# CAN_5V.net
KiCad netlist of a schematic drawn in Altium Designer
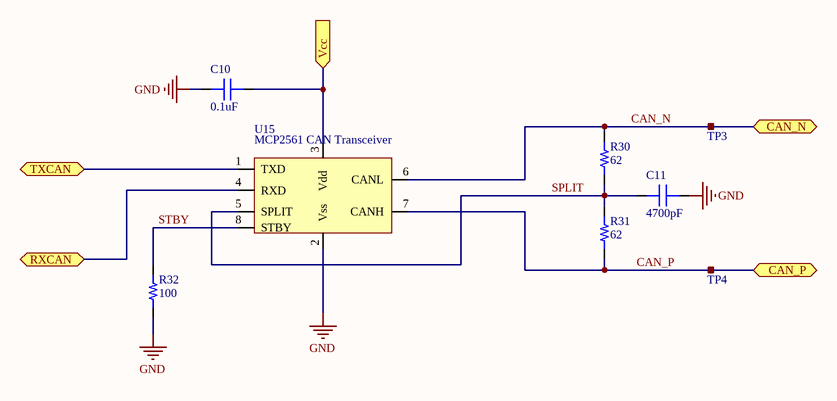
[diagram p0: CAN_5V.SchDoc]

(export (version "E")
  (design (tool "Eeschema 10.0.6"))
  (components
    (comp (ref "C10")
      (value "capacitor")
      (footprint "0603")
      (description "Generic 0603 capacitor")
      (fields (field (name "CAPACITANCE") "0.1uF") (field (name "VOLTAGE") "50"))
      (libsource (lib "altlib") (part "capacitor"))
    )
    (comp (ref "C11")
      (value "capacitor")
      (footprint "0603")
      (description "Generic 0603 capacitor")
      (fields (field (name "CAPACITANCE") "4700pF") (field (name "VOLTAGE") "50"))
      (libsource (lib "altlib") (part "capacitor"))
    )
    (comp (ref "R30")
      (value "resistor")
      (footprint "0603")
      (fields (field (name "RESISTANCE") "62"))
      (libsource (lib "altlib") (part "resistor"))
    )
    (comp (ref "R31")
      (value "resistor")
      (footprint "0603")
      (fields (field (name "RESISTANCE") "62"))
      (libsource (lib "altlib") (part "resistor"))
    )
    (comp (ref "R32")
      (value "resistor")
      (footprint "0603")
      (fields (field (name "RESISTANCE") "100"))
      (libsource (lib "altlib") (part "resistor"))
    )
    (comp (ref "TP3") (value "RCU-0C") (footprint "RCU-0C") (libsource (lib "altlib") (part "RCU-0C")))
    (comp (ref "TP4") (value "RCU-0C") (footprint "RCU-0C") (libsource (lib "altlib") (part "RCU-0C")))
    (comp (ref "U15")
      (value "MCP2561 CAN Transceiver")
      (footprint "SOIC-8")
      (libsource (lib "altlib") (part "MCP2561 CAN Transceiver"))
    )
  )
  (nets
    (net (code "1") (name "/CAN_N") (class "Default")
      (node (ref "R30") (pin "1") (pinfunction "1_1") (pintype "passive"))
      (node (ref "TP3") (pin "1") (pintype "passive"))
      (node (ref "U15") (pin "6") (pinfunction "CANL_6") (pintype "passive"))
    )
    (net (code "2") (name "/CAN_P") (class "Default")
      (node (ref "R31") (pin "2") (pinfunction "2_2") (pintype "passive"))
      (node (ref "TP4") (pin "1") (pintype "passive"))
      (node (ref "U15") (pin "7") (pinfunction "CANH_7") (pintype "passive"))
    )
    (net (code "3") (name "/RXCAN") (class "Default")
      (node (ref "U15") (pin "4") (pinfunction "RXD_4") (pintype "passive"))
    )
    (net (code "4") (name "/SPLIT") (class "Default")
      (node (ref "C11") (pin "1") (pinfunction "1_1") (pintype "passive"))
      (node (ref "R30") (pin "2") (pinfunction "2_2") (pintype "passive"))
      (node (ref "R31") (pin "1") (pinfunction "1_1") (pintype "passive"))
      (node (ref "U15") (pin "5") (pinfunction "SPLIT_5") (pintype "passive"))
    )
    (net (code "5") (name "/STBY") (class "Default")
      (node (ref "R32") (pin "1") (pinfunction "1_1") (pintype "passive"))
      (node (ref "U15") (pin "8") (pinfunction "STBY_8") (pintype "passive"))
    )
    (net (code "6") (name "/TXCAN") (class "Default")
      (node (ref "U15") (pin "1") (pinfunction "TXD_1") (pintype "passive"))
    )
    (net (code "7") (name "/Vcc") (class "Default")
      (node (ref "C10") (pin "2") (pinfunction "2_2") (pintype "passive"))
      (node (ref "U15") (pin "3") (pinfunction "Vdd_3") (pintype "passive"))
    )
    (net (code "8") (name "GND") (class "Default")
      (node (ref "C10") (pin "1") (pinfunction "1_1") (pintype "passive"))
      (node (ref "C11") (pin "2") (pinfunction "2_2") (pintype "passive"))
      (node (ref "R32") (pin "2") (pinfunction "2_2") (pintype "passive"))
      (node (ref "U15") (pin "2") (pinfunction "Vss_2") (pintype "passive"))
    )
  )
)
